# tinyha_relay.net
KiCad netlist of a schematic drawn in EAGLE
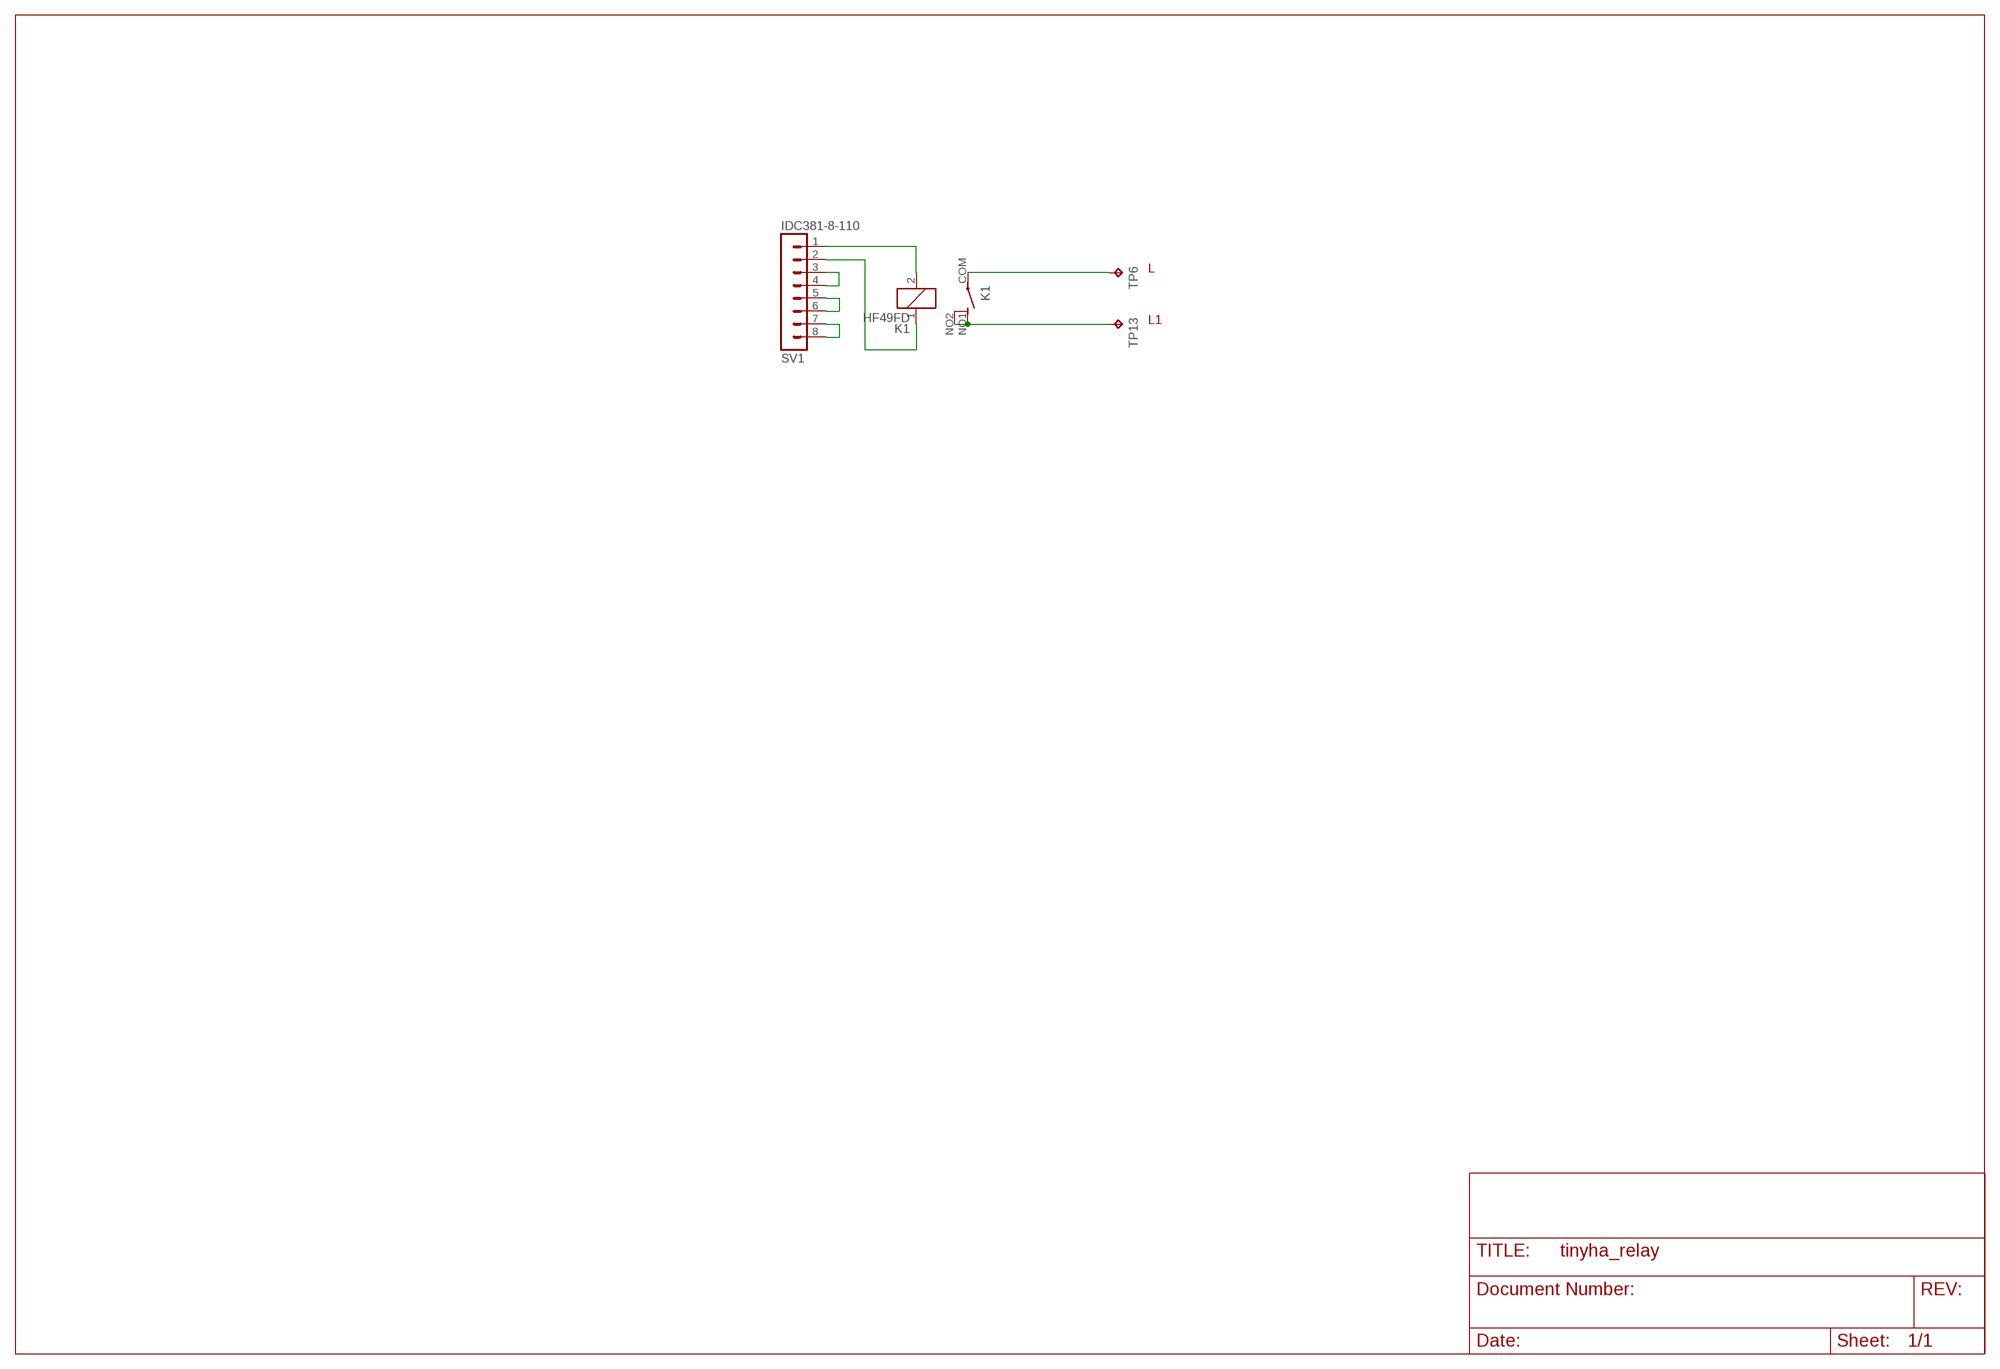
[diagram p0: schematic, sheet 1]

(export (version "E")
  (design (tool "Eeschema 10.0.6"))
  (components
    (comp (ref "K1")
      (value "HF49FD")
      (footprint "eagle-import:HF49D")
      (libsource (lib "eagle-import") (part "HF49FD"))
    )
    (comp (ref "SV1")
      (value "IDC381-8-110")
      (footprint "eagle-import:IDC381-8")
      (libsource (lib "eagle-import") (part "MA08-1-IDC"))
    )
    (comp (ref "TP6")
      (value "TP230")
      (footprint "eagle-import:P1-20")
      (libsource (lib "eagle-import") (part "TP230"))
    )
    (comp (ref "TP13")
      (value "TP230")
      (footprint "eagle-import:P1-20")
      (libsource (lib "eagle-import") (part "TP230"))
    )
  )
  (nets
    (net (code "1") (name "Net-(K1-Pad1)") (class "Default")
      (node (ref "K1") (pin "1") (pinfunction "1_1") (pintype "passive"))
      (node (ref "SV1") (pin "2") (pinfunction "2_2") (pintype "passive"))
    )
    (net (code "2") (name "Net-(K1-Pad2)") (class "Default")
      (node (ref "K1") (pin "2") (pinfunction "2_2") (pintype "passive"))
      (node (ref "SV1") (pin "1") (pinfunction "1_1") (pintype "passive"))
    )
    (net (code "3") (name "Net-(K1B-P)") (class "Default")
      (node (ref "K1") (pin "COM") (pinfunction "P_COM") (pintype "passive"))
      (node (ref "TP6") (pin "TP") (pinfunction "TP_TP") (pintype "input"))
    )
    (net (code "4") (name "Net-(K1B-S1)") (class "Default")
      (node (ref "K1") (pin "NO1") (pinfunction "S1_NO1") (pintype "passive"))
      (node (ref "K1") (pin "NO2") (pinfunction "S2_NO2") (pintype "passive"))
      (node (ref "TP13") (pin "TP") (pinfunction "TP_TP") (pintype "input"))
    )
    (net (code "5") (name "Net-(SV1-Pad3)") (class "Default")
      (node (ref "SV1") (pin "3") (pinfunction "3_3") (pintype "passive"))
      (node (ref "SV1") (pin "4") (pinfunction "4_4") (pintype "passive"))
    )
    (net (code "6") (name "Net-(SV1-Pad5)") (class "Default")
      (node (ref "SV1") (pin "5") (pinfunction "5_5") (pintype "passive"))
      (node (ref "SV1") (pin "6") (pinfunction "6_6") (pintype "passive"))
    )
    (net (code "7") (name "Net-(SV1-Pad7)") (class "Default")
      (node (ref "SV1") (pin "7") (pinfunction "7_7") (pintype "passive"))
      (node (ref "SV1") (pin "8") (pinfunction "8_8") (pintype "passive"))
    )
  )
)
